# tennka4.net
KiCad netlist of a schematic drawn in EAGLE
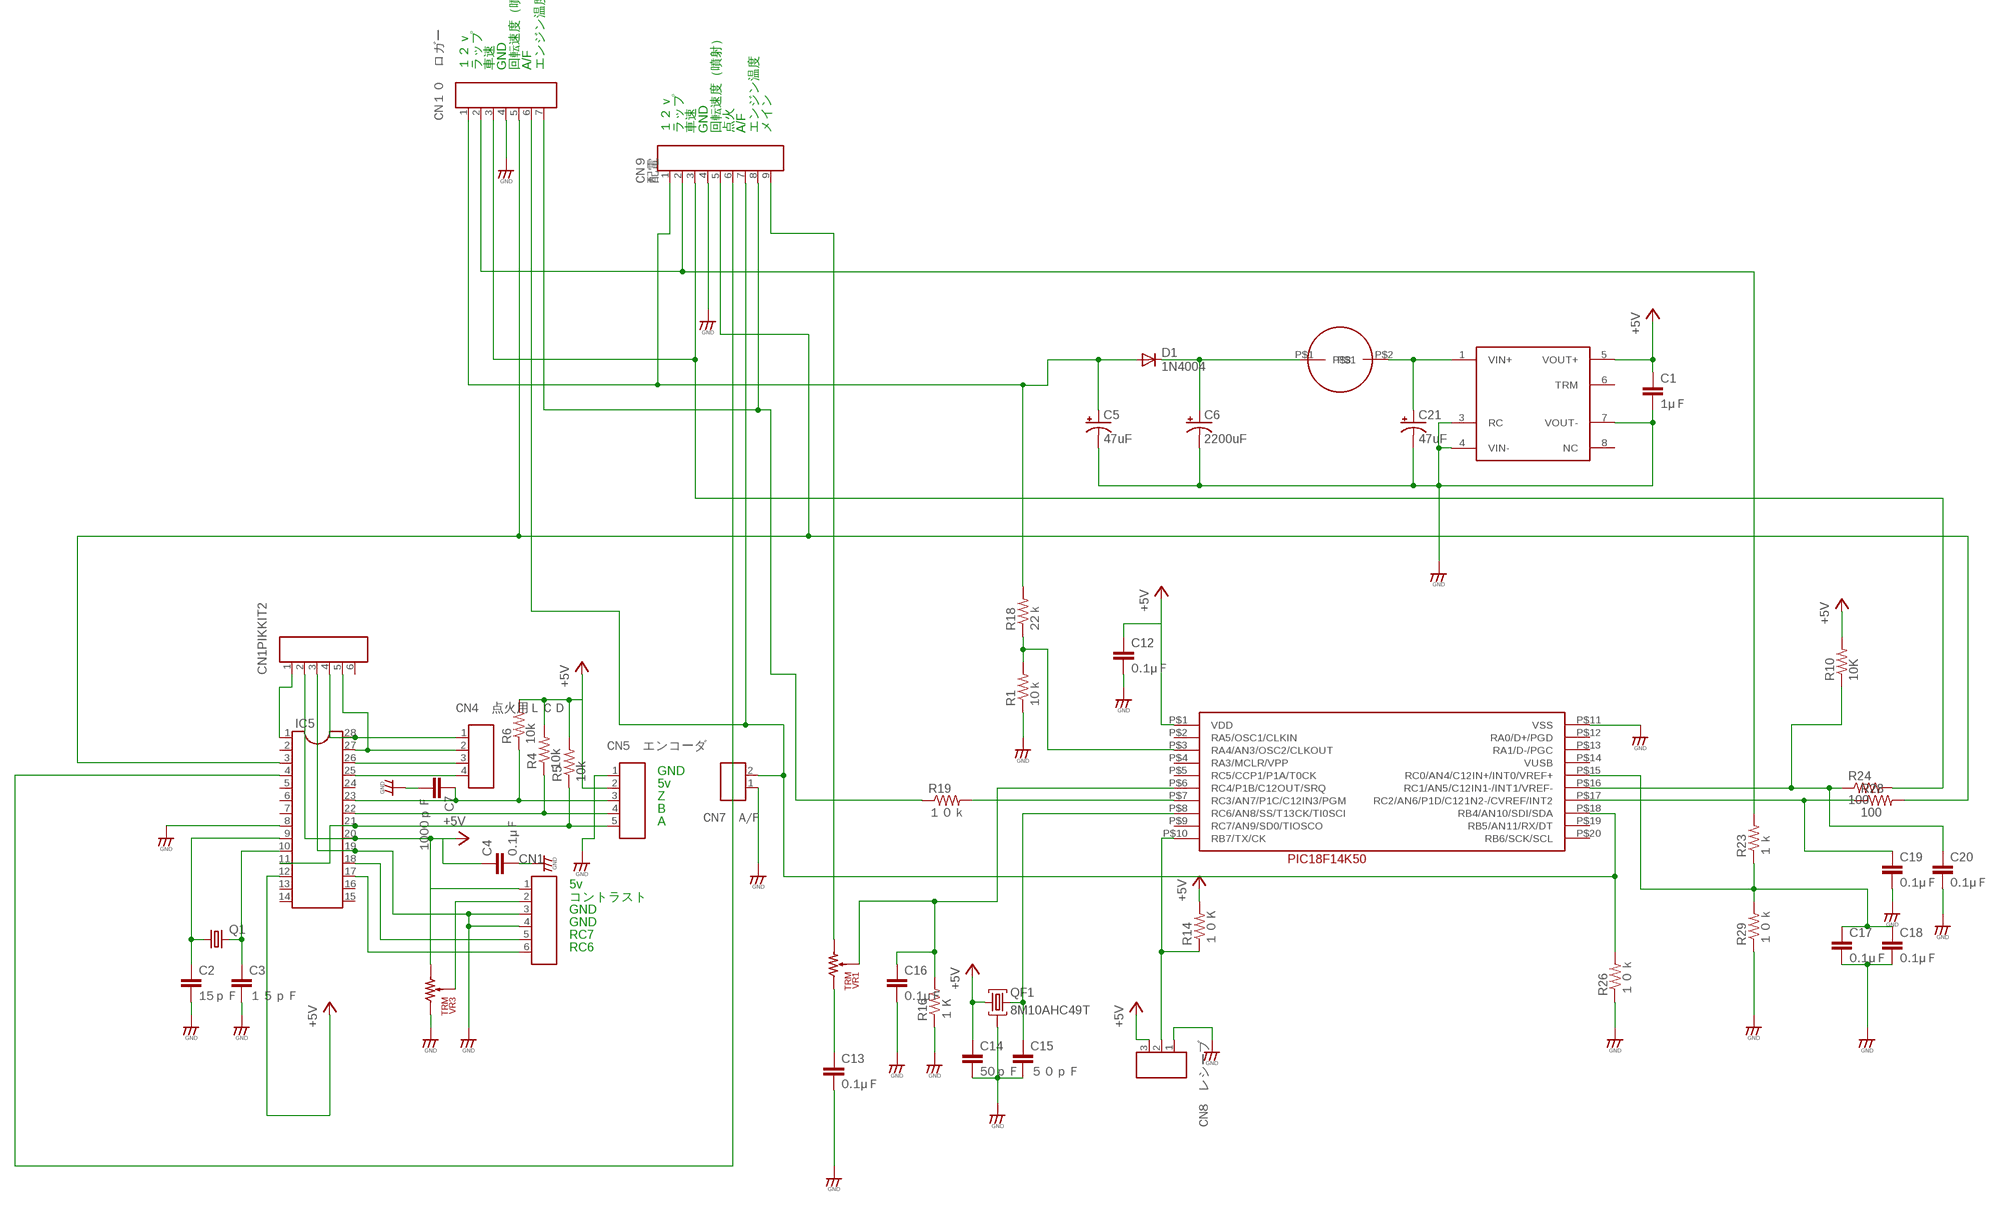
[diagram p0: schematic, sheet 1]

(export (version "E")
  (design (tool "Eeschema 10.0.6"))
  (components
    (comp (ref "C1")
      (value "1μＦ")
      (footprint "eagle-import:C025-024X044")
      (libsource (lib "eagle-import") (part "C-EU025-024X044"))
    )
    (comp (ref "C2")
      (value "15ｐＦ")
      (footprint "eagle-import:C025-024X044")
      (libsource (lib "eagle-import") (part "C-EU025-024X044"))
    )
    (comp (ref "C3")
      (value "１５ｐＦ")
      (footprint "eagle-import:C025-024X044")
      (libsource (lib "eagle-import") (part "C-EU025-024X044"))
    )
    (comp (ref "C4")
      (value "0.1μＦ")
      (footprint "eagle-import:C025-024X044")
      (libsource (lib "eagle-import") (part "C-EU025-024X044"))
    )
    (comp (ref "C5")
      (value "47uF")
      (footprint "eagle-import:E2-4")
      (libsource (lib "eagle-import") (part "CPOL-USE2-4"))
    )
    (comp (ref "C6")
      (value "2200uF")
      (footprint "eagle-import:E5-13")
      (libsource (lib "eagle-import") (part "CPOL-USE5-13"))
    )
    (comp (ref "C7")
      (value "1000ｐＦ")
      (footprint "eagle-import:C025-024X044")
      (libsource (lib "eagle-import") (part "C-EU025-024X044"))
    )
    (comp (ref "C12")
      (value "0.1μＦ")
      (footprint "eagle-import:C025-024X044")
      (libsource (lib "eagle-import") (part "C-EU025-024X044"))
    )
    (comp (ref "C13")
      (value "0.1μＦ")
      (footprint "eagle-import:C025-024X044")
      (libsource (lib "eagle-import") (part "C-EU025-024X044"))
    )
    (comp (ref "C14")
      (value "50ｐＦ")
      (footprint "eagle-import:C025-024X044")
      (libsource (lib "eagle-import") (part "C-EU025-024X044"))
    )
    (comp (ref "C15")
      (value "５０ｐＦ")
      (footprint "eagle-import:C025-024X044")
      (libsource (lib "eagle-import") (part "C-EU025-024X044"))
    )
    (comp (ref "C16")
      (value "0.1μＦ")
      (footprint "eagle-import:C025-024X044")
      (libsource (lib "eagle-import") (part "C-EU025-024X044"))
    )
    (comp (ref "C17")
      (value "0.1μＦ")
      (footprint "eagle-import:C025-024X044")
      (libsource (lib "eagle-import") (part "C-EU025-024X044"))
    )
    (comp (ref "C18")
      (value "0.1μＦ")
      (footprint "eagle-import:C025-024X044")
      (libsource (lib "eagle-import") (part "C-EU025-024X044"))
    )
    (comp (ref "C19")
      (value "0.1μＦ")
      (footprint "eagle-import:C025-024X044")
      (libsource (lib "eagle-import") (part "C-EU025-024X044"))
    )
    (comp (ref "C20")
      (value "0.1μＦ")
      (footprint "eagle-import:C025-024X044")
      (libsource (lib "eagle-import") (part "C-EU025-024X044"))
    )
    (comp (ref "C21")
      (value "47uF")
      (footprint "eagle-import:E2-4")
      (libsource (lib "eagle-import") (part "CPOL-USE2-4"))
    )
    (comp (ref "CN1")
      (value "CON_6P")
      (footprint "eagle-import:CON_HRS_DIP_6")
      (libsource (lib "eagle-import") (part "CON_6P"))
    )
    (comp (ref "CN1PIKKIT2")
      (value "CON_6P")
      (footprint "eagle-import:CON_HRS_DIP_6")
      (libsource (lib "eagle-import") (part "CON_6P"))
    )
    (comp (ref "CN4　点火用ＬＣＤ")
      (value "CON_4P")
      (footprint "eagle-import:CON_HRS_DIP_4")
      (libsource (lib "eagle-import") (part "CON_4P"))
    )
    (comp (ref "CN5　エンコーダ")
      (value "CON_5P")
      (footprint "eagle-import:CON_HRS_DIP_5")
      (libsource (lib "eagle-import") (part "CON_5P"))
    )
    (comp (ref "CN7　A/F")
      (value "CON_2P")
      (footprint "eagle-import:CON_HRS_DIP_2")
      (libsource (lib "eagle-import") (part "CON_2P"))
    )
    (comp (ref "CN8　レシーブ")
      (value "CON_3P")
      (footprint "eagle-import:CON_HRS_DIP_3")
      (libsource (lib "eagle-import") (part "CON_3P"))
    )
    (comp (ref "CN１０　ロガー")
      (value "CON_7P")
      (footprint "eagle-import:CON_HRS_DIP_7")
      (libsource (lib "eagle-import") (part "CON_7P"))
    )
    (comp (ref "CN９")
      (value "配電")
      (footprint "eagle-import:CON_HRS_DIP_9")
      (libsource (lib "eagle-import") (part "CON_9P"))
    )
    (comp (ref "D1")
      (value "1N4004")
      (footprint "eagle-import:DO41-10")
      (libsource (lib "eagle-import") (part "1N4004"))
    )
    (comp (ref "IC5")
      (value "DIL28-3")
      (footprint "eagle-import:DIL28-3")
      (libsource (lib "eagle-import") (part "DIL28-3"))
    )
    (comp (ref "IC6")
      (value "PIC18F14K50")
      (footprint "eagle-import:PIC18F14K50")
      (libsource (lib "eagle-import") (part "PIC18F14K50"))
    )
    (comp (ref "Q1")
      (value "CRYSTALHC49S")
      (footprint "eagle-import:HC49_S")
      (libsource (lib "eagle-import") (part "CRYSTALHC49S"))
    )
    (comp (ref "QF1")
      (value "8M10AHC49T")
      (footprint "eagle-import:HC49U")
      (libsource (lib "eagle-import") (part "8M10AHC49T"))
    )
    (comp (ref "R1")
      (value "10ｋ")
      (footprint "eagle-import:0207_7")
      (libsource (lib "eagle-import") (part "R-US_0207/7"))
    )
    (comp (ref "R4")
      (value "10k")
      (footprint "eagle-import:0207_7")
      (libsource (lib "eagle-import") (part "R-US_0207/7"))
    )
    (comp (ref "R5")
      (value "10k")
      (footprint "eagle-import:0207_7")
      (libsource (lib "eagle-import") (part "R-US_0207/7"))
    )
    (comp (ref "R6")
      (value "10k")
      (footprint "eagle-import:0207_7")
      (libsource (lib "eagle-import") (part "R-US_0207/7"))
    )
    (comp (ref "R10")
      (value "10K")
      (footprint "eagle-import:0207_7")
      (libsource (lib "eagle-import") (part "R-US_0207/7"))
    )
    (comp (ref "R14")
      (value "１０Ｋ")
      (footprint "eagle-import:0207_7")
      (libsource (lib "eagle-import") (part "R-US_0207/7"))
    )
    (comp (ref "R16")
      (value "１Ｋ")
      (footprint "eagle-import:0207_7")
      (libsource (lib "eagle-import") (part "R-US_0207/7"))
    )
    (comp (ref "R18")
      (value "22ｋ")
      (footprint "eagle-import:0207_7")
      (libsource (lib "eagle-import") (part "R-US_0207/7"))
    )
    (comp (ref "R19")
      (value "１０ｋ")
      (footprint "eagle-import:0207_7")
      (libsource (lib "eagle-import") (part "R-US_0207/7"))
    )
    (comp (ref "R23")
      (value "１ｋ")
      (footprint "eagle-import:0207_7")
      (libsource (lib "eagle-import") (part "R-US_0207/7"))
    )
    (comp (ref "R24")
      (value "100")
      (footprint "eagle-import:0207_7")
      (libsource (lib "eagle-import") (part "R-US_0207/7"))
    )
    (comp (ref "R26")
      (value "１０ｋ")
      (footprint "eagle-import:0207_7")
      (libsource (lib "eagle-import") (part "R-US_0207/7"))
    )
    (comp (ref "R28")
      (value "100")
      (footprint "eagle-import:0207_7")
      (libsource (lib "eagle-import") (part "R-US_0207/7"))
    )
    (comp (ref "R29")
      (value "１０ｋ")
      (footprint "eagle-import:0207_7")
      (libsource (lib "eagle-import") (part "R-US_0207/7"))
    )
    (comp (ref "U$3")
      (value "DCDC-CC3-1205SF-E")
      (footprint "eagle-import:DCDC-CC3-1205SF-E")
      (libsource (lib "eagle-import") (part "DCDC-CC3-1205SF-E"))
    )
    (comp (ref "VR1")
      (value "TRM")
      (footprint "eagle-import:TRM")
      (libsource (lib "eagle-import") (part "TRM"))
    )
    (comp (ref "VR3")
      (value "TRM")
      (footprint "eagle-import:TRM")
      (libsource (lib "eagle-import") (part "TRM"))
    )
    (comp (ref "リアクトル")
      (value "INBATERBP")
      (footprint "eagle-import:INBATER101YG")
      (libsource (lib "eagle-import") (part "INBATERBP"))
    )
  )
  (nets
    (net (code "1") (name "+5V") (class "Default")
      (node (ref "C1") (pin "1") (pinfunction "1_1") (pintype "passive"))
      (node (ref "C12") (pin "1") (pinfunction "1_1") (pintype "passive"))
      (node (ref "C14") (pin "1") (pinfunction "1_1") (pintype "passive"))
      (node (ref "C4") (pin "1") (pinfunction "1_1") (pintype "passive"))
      (node (ref "CN1") (pin "1") (pinfunction "1_1") (pintype "passive"))
      (node (ref "CN1PIKKIT2") (pin "2") (pinfunction "2_2") (pintype "passive"))
      (node (ref "CN5　エンコーダ") (pin "2") (pinfunction "2_2") (pintype "passive"))
      (node (ref "CN8　レシーブ") (pin "3") (pinfunction "3_3") (pintype "passive"))
      (node (ref "IC5") (pin "12") (pinfunction "12_12") (pintype "passive"))
      (node (ref "IC5") (pin "20") (pinfunction "20_20") (pintype "passive"))
      (node (ref "IC6") (pin "P$1") (pinfunction "VDD_P$1") (pintype "power_in"))
      (node (ref "QF1") (pin "1") (pinfunction "1_1") (pintype "passive"))
      (node (ref "R10") (pin "2") (pinfunction "2_2") (pintype "passive"))
      (node (ref "R14") (pin "2") (pinfunction "2_2") (pintype "passive"))
      (node (ref "R4") (pin "2") (pinfunction "2_2") (pintype "passive"))
      (node (ref "R5") (pin "2") (pinfunction "2_2") (pintype "passive"))
      (node (ref "R6") (pin "2") (pinfunction "2_2") (pintype "passive"))
      (node (ref "U$3") (pin "5") (pinfunction "VOUT+_5") (pintype "bidirectional"))
      (node (ref "VR3") (pin "P$1") (pinfunction "P$1_P$1") (pintype "passive"))
    )
    (net (code "2") (name "/RA3{slash}MCLR{slash}VPP") (class "Default")
      (node (ref "IC6") (pin "P$4") (pinfunction "RA3/MCLR/VPP_P$4") (pintype "power_in"))
    )
    (net (code "3") (name "GND") (class "Default")
      (node (ref "C1") (pin "2") (pinfunction "2_2") (pintype "passive"))
      (node (ref "C12") (pin "2") (pinfunction "2_2") (pintype "passive"))
      (node (ref "C13") (pin "2") (pinfunction "2_2") (pintype "passive"))
      (node (ref "C14") (pin "2") (pinfunction "2_2") (pintype "passive"))
      (node (ref "C15") (pin "2") (pinfunction "2_2") (pintype "passive"))
      (node (ref "C16") (pin "2") (pinfunction "2_2") (pintype "passive"))
      (node (ref "C17") (pin "2") (pinfunction "2_2") (pintype "passive"))
      (node (ref "C18") (pin "2") (pinfunction "2_2") (pintype "passive"))
      (node (ref "C19") (pin "2") (pinfunction "2_2") (pintype "passive"))
      (node (ref "C2") (pin "2") (pinfunction "2_2") (pintype "passive"))
      (node (ref "C20") (pin "2") (pinfunction "2_2") (pintype "passive"))
      (node (ref "C21") (pin "-") (pinfunction "-_-") (pintype "passive"))
      (node (ref "C3") (pin "2") (pinfunction "2_2") (pintype "passive"))
      (node (ref "C4") (pin "2") (pinfunction "2_2") (pintype "passive"))
      (node (ref "C5") (pin "-") (pinfunction "-_-") (pintype "passive"))
      (node (ref "C6") (pin "-") (pinfunction "-_-") (pintype "passive"))
      (node (ref "C7") (pin "2") (pinfunction "2_2") (pintype "passive"))
      (node (ref "CN1") (pin "3") (pinfunction "3_3") (pintype "passive"))
      (node (ref "CN1") (pin "4") (pinfunction "4_4") (pintype "passive"))
      (node (ref "CN1PIKKIT2") (pin "3") (pinfunction "3_3") (pintype "passive"))
      (node (ref "CN5　エンコーダ") (pin "1") (pinfunction "1_1") (pintype "passive"))
      (node (ref "CN7　A/F") (pin "1") (pinfunction "1_1") (pintype "passive"))
      (node (ref "CN8　レシーブ") (pin "1") (pinfunction "1_1") (pintype "passive"))
      (node (ref "CN１０　ロガー") (pin "4") (pinfunction "4_4") (pintype "passive"))
      (node (ref "CN９") (pin "4") (pinfunction "4_4") (pintype "passive"))
      (node (ref "IC5") (pin "19") (pinfunction "19_19") (pintype "passive"))
      (node (ref "IC5") (pin "8") (pinfunction "8_8") (pintype "passive"))
      (node (ref "IC6") (pin "P$11") (pinfunction "VSS_P$11") (pintype "power_in"))
      (node (ref "QF1") (pin "2") (pinfunction "2_2") (pintype "passive"))
      (node (ref "R1") (pin "1") (pinfunction "1_1") (pintype "passive"))
      (node (ref "R16") (pin "1") (pinfunction "1_1") (pintype "passive"))
      (node (ref "R26") (pin "1") (pinfunction "1_1") (pintype "passive"))
      (node (ref "R29") (pin "1") (pinfunction "1_1") (pintype "passive"))
      (node (ref "U$3") (pin "3") (pinfunction "RC_3") (pintype "bidirectional"))
      (node (ref "U$3") (pin "4") (pinfunction "VIN-_4") (pintype "bidirectional"))
      (node (ref "U$3") (pin "7") (pinfunction "VOUT-_7") (pintype "bidirectional"))
      (node (ref "VR3") (pin "P$3") (pinfunction "P$3_P$3") (pintype "passive"))
    )
    (net (code "4") (name "Net-(C2-Pad1)") (class "Default")
      (node (ref "C2") (pin "1") (pinfunction "1_1") (pintype "passive"))
      (node (ref "IC5") (pin "9") (pinfunction "9_9") (pintype "passive"))
      (node (ref "Q1") (pin "1") (pinfunction "1_1") (pintype "passive"))
    )
    (net (code "5") (name "Net-(C3-Pad1)") (class "Default")
      (node (ref "C3") (pin "1") (pinfunction "1_1") (pintype "passive"))
      (node (ref "IC5") (pin "10") (pinfunction "10_10") (pintype "passive"))
      (node (ref "Q1") (pin "2") (pinfunction "2_2") (pintype "passive"))
    )
    (net (code "6") (name "Net-(C5-Pad+)") (class "Default")
      (node (ref "C5") (pin "+") (pinfunction "+_+") (pintype "passive"))
      (node (ref "CN１０　ロガー") (pin "1") (pinfunction "1_1") (pintype "passive"))
      (node (ref "CN９") (pin "1") (pinfunction "1_1") (pintype "passive"))
      (node (ref "D1") (pin "A") (pinfunction "A_A") (pintype "passive"))
      (node (ref "R18") (pin "2") (pinfunction "2_2") (pintype "passive"))
    )
    (net (code "7") (name "Net-(C6-Pad+)") (class "Default")
      (node (ref "C6") (pin "+") (pinfunction "+_+") (pintype "passive"))
      (node (ref "D1") (pin "C") (pinfunction "C_C") (pintype "passive"))
      (node (ref "リアクトル") (pin "P$1") (pinfunction "P$1_P$1") (pintype "bidirectional"))
    )
    (net (code "8") (name "Net-(C7-Pad1)") (class "Default")
      (node (ref "C7") (pin "1") (pinfunction "1_1") (pintype "passive"))
      (node (ref "CN5　エンコーダ") (pin "3") (pinfunction "3_3") (pintype "passive"))
      (node (ref "IC5") (pin "23") (pinfunction "23_23") (pintype "passive"))
      (node (ref "R6") (pin "1") (pinfunction "1_1") (pintype "passive"))
    )
    (net (code "9") (name "Net-(C13-Pad1)") (class "Default")
      (node (ref "C13") (pin "1") (pinfunction "1_1") (pintype "passive"))
      (node (ref "VR1") (pin "P$3") (pinfunction "P$3_P$3") (pintype "passive"))
    )
    (net (code "10") (name "Net-(CN1-Pad2)") (class "Default")
      (node (ref "CN1") (pin "2") (pinfunction "2_2") (pintype "passive"))
      (node (ref "VR3") (pin "P$2") (pinfunction "P$2_P$2") (pintype "passive"))
    )
    (net (code "11") (name "Net-(CN1-Pad5)") (class "Default")
      (node (ref "CN1") (pin "5") (pinfunction "5_5") (pintype "passive"))
      (node (ref "IC5") (pin "18") (pinfunction "18_18") (pintype "passive"))
    )
    (net (code "12") (name "Net-(CN1-Pad6)") (class "Default")
      (node (ref "CN1") (pin "6") (pinfunction "6_6") (pintype "passive"))
      (node (ref "IC5") (pin "17") (pinfunction "17_17") (pintype "passive"))
    )
    (net (code "13") (name "Net-(CN1PIKKIT2-Pad1)") (class "Default")
      (node (ref "CN1PIKKIT2") (pin "1") (pinfunction "1_1") (pintype "passive"))
      (node (ref "IC5") (pin "1") (pinfunction "1_1") (pintype "passive"))
    )
    (net (code "14") (name "Net-(CN1PIKKIT2-Pad4)") (class "Default")
      (node (ref "CN1PIKKIT2") (pin "4") (pinfunction "4_4") (pintype "passive"))
      (node (ref "CN4　点火用ＬＣＤ") (pin "1") (pinfunction "1_1") (pintype "passive"))
      (node (ref "IC5") (pin "28") (pinfunction "28_28") (pintype "passive"))
    )
    (net (code "15") (name "Net-(CN1PIKKIT2-Pad5)") (class "Default")
      (node (ref "CN1PIKKIT2") (pin "5") (pinfunction "5_5") (pintype "passive"))
      (node (ref "CN4　点火用ＬＣＤ") (pin "2") (pinfunction "2_2") (pintype "passive"))
      (node (ref "IC5") (pin "27") (pinfunction "27_27") (pintype "passive"))
    )
    (net (code "16") (name "Net-(CN4　点火用ＬＣＤ-Pad3)") (class "Default")
      (node (ref "CN4　点火用ＬＣＤ") (pin "3") (pinfunction "3_3") (pintype "passive"))
      (node (ref "IC5") (pin "26") (pinfunction "26_26") (pintype "passive"))
    )
    (net (code "17") (name "Net-(CN4　点火用ＬＣＤ-Pad4)") (class "Default")
      (node (ref "CN4　点火用ＬＣＤ") (pin "4") (pinfunction "4_4") (pintype "passive"))
      (node (ref "IC5") (pin "25") (pinfunction "25_25") (pintype "passive"))
    )
    (net (code "18") (name "Net-(CN5　エンコーダ-Pad4)") (class "Default")
      (node (ref "CN5　エンコーダ") (pin "4") (pinfunction "4_4") (pintype "passive"))
      (node (ref "IC5") (pin "22") (pinfunction "22_22") (pintype "passive"))
      (node (ref "R4") (pin "1") (pinfunction "1_1") (pintype "passive"))
    )
    (net (code "19") (name "Net-(CN5　エンコーダ-Pad5)") (class "Default")
      (node (ref "CN5　エンコーダ") (pin "5") (pinfunction "5_5") (pintype "passive"))
      (node (ref "IC5") (pin "11") (pinfunction "11_11") (pintype "passive"))
      (node (ref "IC5") (pin "21") (pinfunction "21_21") (pintype "passive"))
      (node (ref "R5") (pin "1") (pinfunction "1_1") (pintype "passive"))
    )
    (net (code "20") (name "Net-(CN１０　ロガー-Pad2)") (class "Default")
      (node (ref "CN１０　ロガー") (pin "2") (pinfunction "2_2") (pintype "passive"))
      (node (ref "CN９") (pin "2") (pinfunction "2_2") (pintype "passive"))
      (node (ref "R23") (pin "2") (pinfunction "2_2") (pintype "passive"))
    )
    (net (code "21") (name "Net-(CN１０　ロガー-Pad3)") (class "Default")
      (node (ref "CN１０　ロガー") (pin "3") (pinfunction "3_3") (pintype "passive"))
      (node (ref "CN９") (pin "3") (pinfunction "3_3") (pintype "passive"))
      (node (ref "R24") (pin "2") (pinfunction "2_2") (pintype "passive"))
    )
    (net (code "22") (name "Net-(CN１０　ロガー-Pad5)") (class "Default")
      (node (ref "CN１０　ロガー") (pin "5") (pinfunction "5_5") (pintype "passive"))
      (node (ref "CN９") (pin "5") (pinfunction "5_5") (pintype "passive"))
      (node (ref "IC5") (pin "3") (pinfunction "3_3") (pintype "passive"))
      (node (ref "R28") (pin "2") (pinfunction "2_2") (pintype "passive"))
    )
    (net (code "23") (name "Net-(CN１０　ロガー-Pad7)") (class "Default")
      (node (ref "CN１０　ロガー") (pin "7") (pinfunction "7_7") (pintype "passive"))
      (node (ref "CN９") (pin "8") (pinfunction "8_8") (pintype "passive"))
      (node (ref "R19") (pin "1") (pinfunction "1_1") (pintype "passive"))
    )
    (net (code "24") (name "Net-(CN９-Pad6)") (class "Default")
      (node (ref "CN９") (pin "6") (pinfunction "6_6") (pintype "passive"))
      (node (ref "IC5") (pin "4") (pinfunction "4_4") (pintype "passive"))
    )
    (net (code "25") (name "Net-(CN９-Pad9)") (class "Default")
      (node (ref "CN９") (pin "9") (pinfunction "9_9") (pintype "passive"))
      (node (ref "VR1") (pin "P$1") (pinfunction "P$1_P$1") (pintype "passive"))
    )
    (net (code "26") (name "Net-(IC6-RA4{slash}AN3{slash}OSC2{slash}CLKOUT)") (class "Default")
      (node (ref "IC6") (pin "P$3") (pinfunction "RA4/AN3/OSC2/CLKOUT_P$3") (pintype "bidirectional"))
      (node (ref "R1") (pin "2") (pinfunction "2_2") (pintype "passive"))
      (node (ref "R18") (pin "1") (pinfunction "1_1") (pintype "passive"))
    )
    (net (code "27") (name "Net-(IC6-RB4{slash}AN10{slash}SDI{slash}SDA)") (class "Default")
      (node (ref "CN7　A/F") (pin "2") (pinfunction "2_2") (pintype "passive"))
      (node (ref "CN１０　ロガー") (pin "6") (pinfunction "6_6") (pintype "passive"))
      (node (ref "CN９") (pin "7") (pinfunction "7_7") (pintype "passive"))
      (node (ref "IC6") (pin "P$18") (pinfunction "RB4/AN10/SDI/SDA_P$18") (pintype "bidirectional"))
      (node (ref "R26") (pin "2") (pinfunction "2_2") (pintype "passive"))
    )
    (net (code "28") (name "Net-(IC6-RB7{slash}TX{slash}CK)") (class "Default")
      (node (ref "CN8　レシーブ") (pin "2") (pinfunction "2_2") (pintype "passive"))
      (node (ref "IC6") (pin "P$10") (pinfunction "RB7/TX/CK_P$10") (pintype "bidirectional"))
      (node (ref "R14") (pin "1") (pinfunction "1_1") (pintype "passive"))
    )
    (net (code "29") (name "Net-(IC6-RC0{slash}AN4{slash}C12IN+{slash}INT0{slash}VREF+)") (class "Default")
      (node (ref "C17") (pin "1") (pinfunction "1_1") (pintype "passive"))
      (node (ref "C18") (pin "1") (pinfunction "1_1") (pintype "passive"))
      (node (ref "IC6") (pin "P$15") (pinfunction "RC0/AN4/C12IN+/INT0/VREF+_P$15") (pintype "input"))
      (node (ref "R23") (pin "1") (pinfunction "1_1") (pintype "passive"))
      (node (ref "R29") (pin "2") (pinfunction "2_2") (pintype "passive"))
    )
    (net (code "30") (name "Net-(IC6-RC1{slash}AN5{slash}C12IN1-{slash}INT1{slash}VREF-)") (class "Default")
      (node (ref "C20") (pin "1") (pinfunction "1_1") (pintype "passive"))
      (node (ref "IC6") (pin "P$16") (pinfunction "RC1/AN5/C12IN1-/INT1/VREF-_P$16") (pintype "bidirectional"))
      (node (ref "R10") (pin "1") (pinfunction "1_1") (pintype "passive"))
      (node (ref "R24") (pin "1") (pinfunction "1_1") (pintype "passive"))
    )
    (net (code "31") (name "Net-(IC6-RC2{slash}AN6{slash}P1D{slash}C121N2-{slash}CVREF{slash}INT2)") (class "Default")
      (node (ref "C19") (pin "1") (pinfunction "1_1") (pintype "passive"))
      (node (ref "IC6") (pin "P$17") (pinfunction "RC2/AN6/P1D/C121N2-/CVREF/INT2_P$17") (pintype "bidirectional"))
      (node (ref "R28") (pin "1") (pinfunction "1_1") (pintype "passive"))
    )
    (net (code "32") (name "Net-(IC6-RC3{slash}AN7{slash}P1C{slash}C12IN3{slash}PGM)") (class "Default")
      (node (ref "IC6") (pin "P$7") (pinfunction "RC3/AN7/P1C/C12IN3/PGM_P$7") (pintype "bidirectional"))
      (node (ref "R19") (pin "2") (pinfunction "2_2") (pintype "passive"))
    )
    (net (code "33") (name "Net-(IC6-RC4{slash}P1B{slash}C12OUT{slash}SRQ)") (class "Default")
      (node (ref "C16") (pin "1") (pinfunction "1_1") (pintype "passive"))
      (node (ref "IC6") (pin "P$6") (pinfunction "RC4/P1B/C12OUT/SRQ_P$6") (pintype "bidirectional"))
      (node (ref "R16") (pin "2") (pinfunction "2_2") (pintype "passive"))
      (node (ref "VR1") (pin "P$2") (pinfunction "P$2_P$2") (pintype "passive"))
    )
    (net (code "34") (name "Net-(IC6-RC6{slash}AN8{slash}SS{slash}T13CK{slash}TI0SCI)") (class "Default")
      (node (ref "C15") (pin "1") (pinfunction "1_1") (pintype "passive"))
      (node (ref "IC6") (pin "P$8") (pinfunction "RC6/AN8/SS/T13CK/TI0SCI_P$8") (pintype "bidirectional"))
      (node (ref "QF1") (pin "3") (pinfunction "3_3") (pintype "passive"))
    )
    (net (code "35") (name "Net-(U$3-VIN+)") (class "Default")
      (node (ref "C21") (pin "+") (pinfunction "+_+") (pintype "passive"))
      (node (ref "U$3") (pin "1") (pinfunction "VIN+_1") (pintype "bidirectional"))
      (node (ref "リアクトル") (pin "P$2") (pinfunction "P$3_P$2") (pintype "bidirectional"))
    )
    (net (code "36") (name "unconnected-(CN1PIKKIT2-Pad6)") (class "Default")
      (node (ref "CN1PIKKIT2") (pin "6") (pinfunction "6_6") (pintype "passive"))
    )
    (net (code "37") (name "unconnected-(IC5-Pad2)") (class "Default")
      (node (ref "IC5") (pin "2") (pinfunction "2_2") (pintype "passive"))
    )
    (net (code "38") (name "unconnected-(IC5-Pad5)") (class "Default")
      (node (ref "IC5") (pin "5") (pinfunction "5_5") (pintype "passive"))
    )
    (net (code "39") (name "unconnected-(IC5-Pad6)") (class "Default")
      (node (ref "IC5") (pin "6") (pinfunction "6_6") (pintype "passive"))
    )
    (net (code "40") (name "unconnected-(IC5-Pad7)") (class "Default")
      (node (ref "IC5") (pin "7") (pinfunction "7_7") (pintype "passive"))
    )
    (net (code "41") (name "unconnected-(IC5-Pad13)") (class "Default")
      (node (ref "IC5") (pin "13") (pinfunction "13_13") (pintype "passive"))
    )
    (net (code "42") (name "unconnected-(IC5-Pad14)") (class "Default")
      (node (ref "IC5") (pin "14") (pinfunction "14_14") (pintype "passive"))
    )
    (net (code "43") (name "unconnected-(IC5-Pad15)") (class "Default")
      (node (ref "IC5") (pin "15") (pinfunction "15_15") (pintype "passive"))
    )
    (net (code "44") (name "unconnected-(IC5-Pad16)") (class "Default")
      (node (ref "IC5") (pin "16") (pinfunction "16_16") (pintype "passive"))
    )
    (net (code "45") (name "unconnected-(IC5-Pad24)") (class "Default")
      (node (ref "IC5") (pin "24") (pinfunction "24_24") (pintype "passive"))
    )
    (net (code "46") (name "unconnected-(IC6-RA0{slash}D+{slash}PGD-PadP$12)") (class "Default")
      (node (ref "IC6") (pin "P$12") (pinfunction "RA0/D+/PGD_P$12") (pintype "bidirectional"))
    )
    (net (code "47") (name "unconnected-(IC6-RA1{slash}D-{slash}PGC-PadP$13)") (class "Default")
      (node (ref "IC6") (pin "P$13") (pinfunction "RA1/D-/PGC_P$13") (pintype "bidirectional"))
    )
    (net (code "48") (name "unconnected-(IC6-RA5{slash}OSC1{slash}CLKIN-PadP$2)") (class "Default")
      (node (ref "IC6") (pin "P$2") (pinfunction "RA5/OSC1/CLKIN_P$2") (pintype "bidirectional"))
    )
    (net (code "49") (name "unconnected-(IC6-RB5{slash}AN11{slash}RX{slash}DT-PadP$19)") (class "Default")
      (node (ref "IC6") (pin "P$19") (pinfunction "RB5/AN11/RX/DT_P$19") (pintype "bidirectional"))
    )
    (net (code "50") (name "unconnected-(IC6-RB6{slash}SCK{slash}SCL-PadP$20)") (class "Default")
      (node (ref "IC6") (pin "P$20") (pinfunction "RB6/SCK/SCL_P$20") (pintype "bidirectional"))
    )
    (net (code "51") (name "unconnected-(IC6-RC5{slash}CCP1{slash}P1A{slash}T0CK-PadP$5)") (class "Default")
      (node (ref "IC6") (pin "P$5") (pinfunction "RC5/CCP1/P1A/T0CK_P$5") (pintype "bidirectional"))
    )
    (net (code "52") (name "unconnected-(IC6-RC7{slash}AN9{slash}SD0{slash}TIOSCO-PadP$9)") (class "Default")
      (node (ref "IC6") (pin "P$9") (pinfunction "RC7/AN9/SD0/TIOSCO_P$9") (pintype "bidirectional"))
    )
    (net (code "53") (name "unconnected-(IC6-VUSB-PadP$14)") (class "Default")
      (node (ref "IC6") (pin "P$14") (pinfunction "VUSB_P$14") (pintype "bidirectional"))
    )
    (net (code "54") (name "unconnected-(U$3-NC-Pad8)") (class "Default")
      (node (ref "U$3") (pin "8") (pinfunction "NC_8") (pintype "bidirectional"))
    )
    (net (code "55") (name "unconnected-(U$3-TRM-Pad6)") (class "Default")
      (node (ref "U$3") (pin "6") (pinfunction "TRM_6") (pintype "bidirectional"))
    )
  )
)
